# Hrafn_Top.net
KiCad netlist of a schematic drawn in Altium Designer
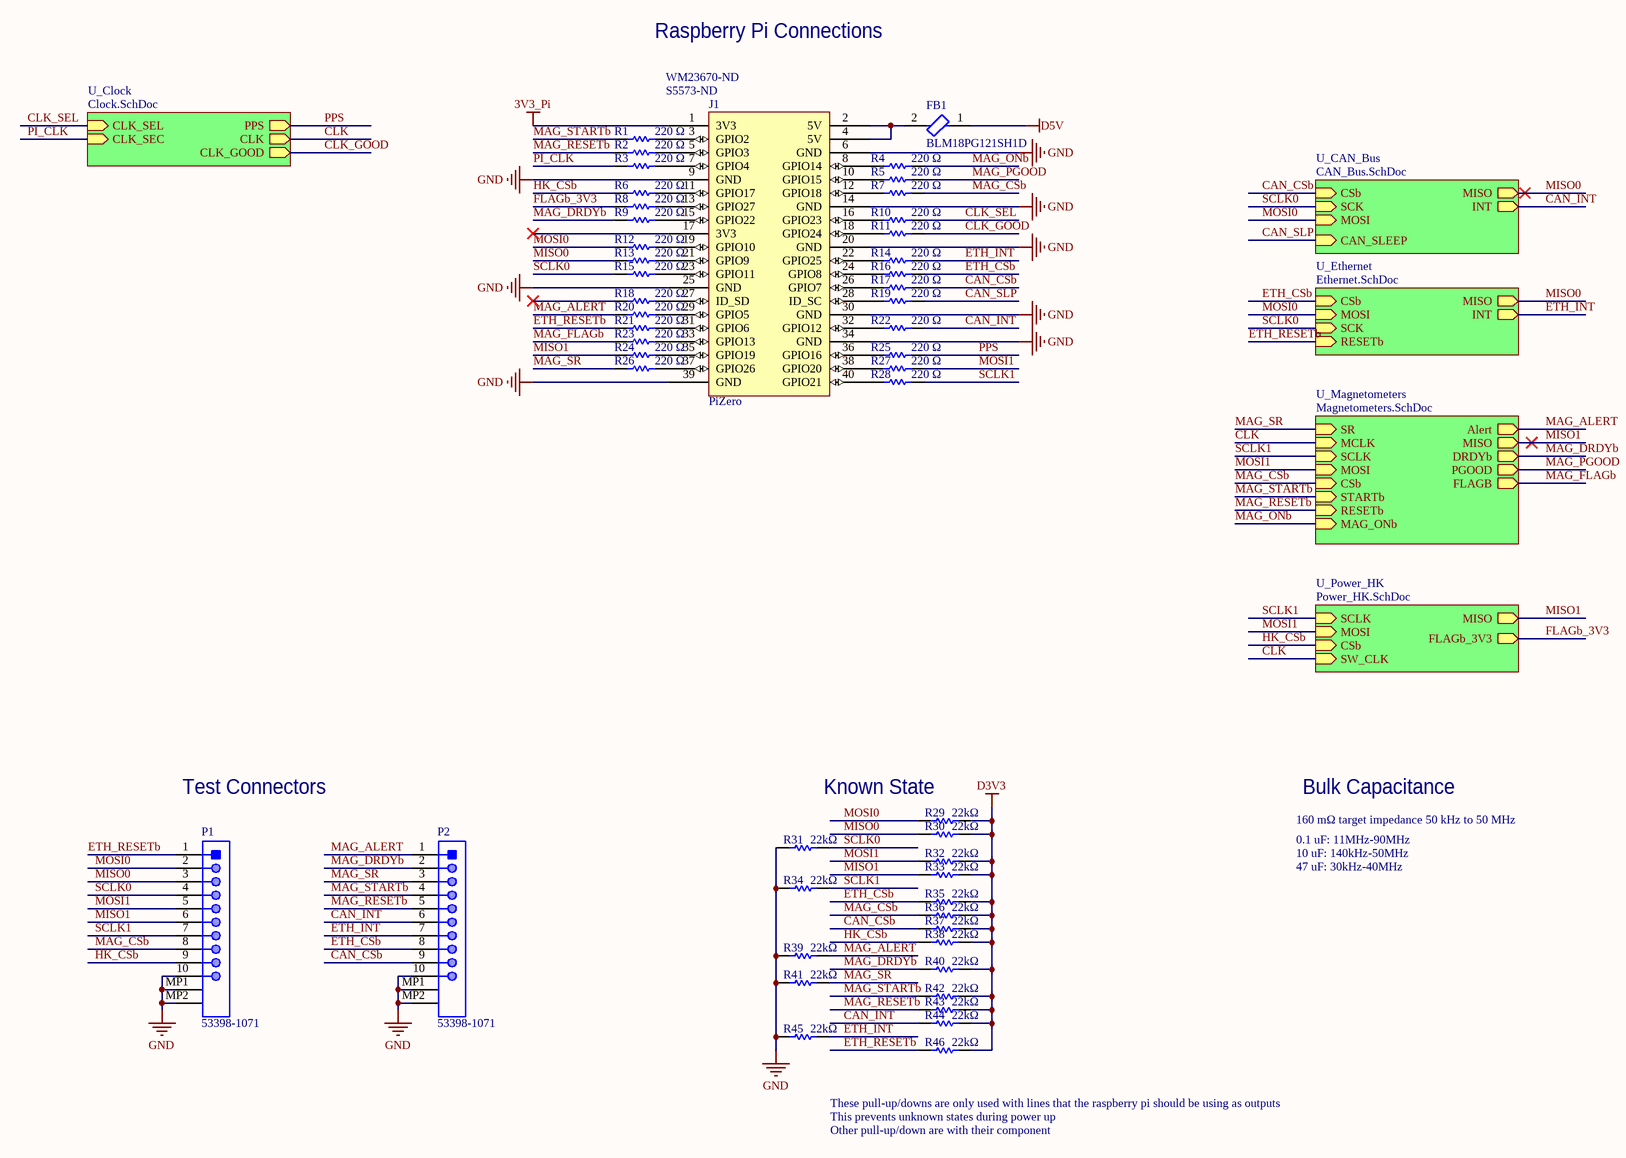
[diagram p0: Hrafn_Top.SchDoc]

(export (version "E")
  (design (tool "Eeschema 10.0.6"))
  (components
    (comp (ref "FB1")
      (value "BLM18PG121SH1D")
      (footprint "FP-BLM18-0_15-t0_8-IPC_C")
      (description "Chip Ferrite Bead, 0603, 120Ω @ 100MHz, 0.05Ω, 25%, 2A")
      (fields (field (name "TOLERANCE") "25%"))
      (libsource (lib "Altium Content Vault") (part "5f30dd21d616792df468990f7003faa"))
    )
    (comp (ref "J1")
      (value "PiZero")
      (footprint "DIP40")
      (fields
        (field (name "SUPPLIER PART NUMBER 1") "S5573-ND")
        (field (name "SUPPLIER PART NUMBER 2") "WM23670-ND")
      )
      (libsource (lib "Hrafn") (part "PiZero"))
    )
    (comp (ref "P1")
      (value "53398-1071")
      (footprint "MOLX-53398-1071_V")
      (description "Male Header, Pitch 1.25 mm, 1 x 10 Position, Height 4.7 mm, -40 to 85 degC, RoHS, Tape and Reel")
      (fields (field (name "MANUFACTURER") "Molex"))
      (libsource (lib "Altium Content Vault") (part "CN-1P-2M-R10"))
    )
    (comp (ref "P2")
      (value "53398-1071")
      (footprint "MOLX-53398-1071_V")
      (description "Male Header, Pitch 1.25 mm, 1 x 10 Position, Height 4.7 mm, -40 to 85 degC, RoHS, Tape and Reel")
      (fields (field (name "MANUFACTURER") "Molex"))
      (libsource (lib "Altium Content Vault") (part "CN-1P-2M-R10"))
    )
    (comp (ref "R1")
      (value "220 Ω")
      (footprint "RESC1005X40X25LL05T05")
      (fields (field (name "PART NUMBER") "CRCW040220K0FKED") (field (name "MANUFACTURER") "Vishay Dale"))
      (libsource (lib "Altium Content Vault") (part "RES"))
    )
    (comp (ref "R2")
      (value "220 Ω")
      (footprint "RESC1005X40X25LL05T05")
      (fields (field (name "PART NUMBER") "CRCW040220K0FKED") (field (name "MANUFACTURER") "Vishay Dale"))
      (libsource (lib "Altium Content Vault") (part "RES"))
    )
    (comp (ref "R3")
      (value "220 Ω")
      (footprint "RESC1005X40X25LL05T05")
      (fields (field (name "PART NUMBER") "CRCW040220K0FKED") (field (name "MANUFACTURER") "Vishay Dale"))
      (libsource (lib "Altium Content Vault") (part "RES"))
    )
    (comp (ref "R4")
      (value "220 Ω")
      (footprint "RESC1005X40X25LL05T05")
      (fields (field (name "PART NUMBER") "CRCW040220K0FKED") (field (name "MANUFACTURER") "Vishay Dale"))
      (libsource (lib "Altium Content Vault") (part "RES"))
    )
    (comp (ref "R5")
      (value "220 Ω")
      (footprint "RESC1005X40X25LL05T05")
      (fields (field (name "PART NUMBER") "CRCW040220K0FKED") (field (name "MANUFACTURER") "Vishay Dale"))
      (libsource (lib "Altium Content Vault") (part "RES"))
    )
    (comp (ref "R6")
      (value "220 Ω")
      (footprint "RESC1005X40X25LL05T05")
      (fields (field (name "PART NUMBER") "CRCW040220K0FKED") (field (name "MANUFACTURER") "Vishay Dale"))
      (libsource (lib "Altium Content Vault") (part "RES"))
    )
    (comp (ref "R7")
      (value "220 Ω")
      (footprint "RESC1005X40X25LL05T05")
      (fields (field (name "PART NUMBER") "CRCW040220K0FKED") (field (name "MANUFACTURER") "Vishay Dale"))
      (libsource (lib "Altium Content Vault") (part "RES"))
    )
    (comp (ref "R8")
      (value "220 Ω")
      (footprint "RESC1005X40X25LL05T05")
      (fields (field (name "PART NUMBER") "CRCW040220K0FKED") (field (name "MANUFACTURER") "Vishay Dale"))
      (libsource (lib "Altium Content Vault") (part "RES"))
    )
    (comp (ref "R9")
      (value "220 Ω")
      (footprint "RESC1005X40X25LL05T05")
      (fields (field (name "PART NUMBER") "CRCW040220K0FKED") (field (name "MANUFACTURER") "Vishay Dale"))
      (libsource (lib "Altium Content Vault") (part "RES"))
    )
    (comp (ref "R10")
      (value "220 Ω")
      (footprint "RESC1005X40X25LL05T05")
      (fields (field (name "PART NUMBER") "CRCW040220K0FKED") (field (name "MANUFACTURER") "Vishay Dale"))
      (libsource (lib "Altium Content Vault") (part "RES"))
    )
    (comp (ref "R11")
      (value "220 Ω")
      (footprint "RESC1005X40X25LL05T05")
      (fields (field (name "PART NUMBER") "CRCW040220K0FKED") (field (name "MANUFACTURER") "Vishay Dale"))
      (libsource (lib "Altium Content Vault") (part "RES"))
    )
    (comp (ref "R12")
      (value "220 Ω")
      (footprint "RESC1005X40X25LL05T05")
      (fields (field (name "PART NUMBER") "CRCW040220K0FKED") (field (name "MANUFACTURER") "Vishay Dale"))
      (libsource (lib "Altium Content Vault") (part "RES"))
    )
    (comp (ref "R13")
      (value "220 Ω")
      (footprint "RESC1005X40X25LL05T05")
      (fields (field (name "PART NUMBER") "CRCW040220K0FKED") (field (name "MANUFACTURER") "Vishay Dale"))
      (libsource (lib "Altium Content Vault") (part "RES"))
    )
    (comp (ref "R14")
      (value "220 Ω")
      (footprint "RESC1005X40X25LL05T05")
      (fields (field (name "PART NUMBER") "CRCW040220K0FKED") (field (name "MANUFACTURER") "Vishay Dale"))
      (libsource (lib "Altium Content Vault") (part "RES"))
    )
    (comp (ref "R15")
      (value "220 Ω")
      (footprint "RESC1005X40X25LL05T05")
      (fields (field (name "PART NUMBER") "CRCW040220K0FKED") (field (name "MANUFACTURER") "Vishay Dale"))
      (libsource (lib "Altium Content Vault") (part "RES"))
    )
    (comp (ref "R16")
      (value "220 Ω")
      (footprint "RESC1005X40X25LL05T05")
      (fields (field (name "PART NUMBER") "CRCW040220K0FKED") (field (name "MANUFACTURER") "Vishay Dale"))
      (libsource (lib "Altium Content Vault") (part "RES"))
    )
    (comp (ref "R17")
      (value "220 Ω")
      (footprint "RESC1005X40X25LL05T05")
      (fields (field (name "PART NUMBER") "CRCW040220K0FKED") (field (name "MANUFACTURER") "Vishay Dale"))
      (libsource (lib "Altium Content Vault") (part "RES"))
    )
    (comp (ref "R18")
      (value "220 Ω")
      (footprint "RESC1005X40X25LL05T05")
      (fields (field (name "PART NUMBER") "CRCW040220K0FKED") (field (name "MANUFACTURER") "Vishay Dale"))
      (libsource (lib "Altium Content Vault") (part "RES"))
    )
    (comp (ref "R19")
      (value "220 Ω")
      (footprint "RESC1005X40X25LL05T05")
      (fields (field (name "PART NUMBER") "CRCW040220K0FKED") (field (name "MANUFACTURER") "Vishay Dale"))
      (libsource (lib "Altium Content Vault") (part "RES"))
    )
    (comp (ref "R20")
      (value "220 Ω")
      (footprint "RESC1005X40X25LL05T05")
      (fields (field (name "PART NUMBER") "CRCW040220K0FKED") (field (name "MANUFACTURER") "Vishay Dale"))
      (libsource (lib "Altium Content Vault") (part "RES"))
    )
    (comp (ref "R21")
      (value "220 Ω")
      (footprint "RESC1005X40X25LL05T05")
      (fields (field (name "PART NUMBER") "CRCW040220K0FKED") (field (name "MANUFACTURER") "Vishay Dale"))
      (libsource (lib "Altium Content Vault") (part "RES"))
    )
    (comp (ref "R22")
      (value "220 Ω")
      (footprint "RESC1005X40X25LL05T05")
      (fields (field (name "PART NUMBER") "CRCW040220K0FKED") (field (name "MANUFACTURER") "Vishay Dale"))
      (libsource (lib "Altium Content Vault") (part "RES"))
    )
    (comp (ref "R23")
      (value "220 Ω")
      (footprint "RESC1005X40X25LL05T05")
      (fields (field (name "PART NUMBER") "CRCW040220K0FKED") (field (name "MANUFACTURER") "Vishay Dale"))
      (libsource (lib "Altium Content Vault") (part "RES"))
    )
    (comp (ref "R24")
      (value "220 Ω")
      (footprint "RESC1005X40X25LL05T05")
      (fields (field (name "PART NUMBER") "CRCW040220K0FKED") (field (name "MANUFACTURER") "Vishay Dale"))
      (libsource (lib "Altium Content Vault") (part "RES"))
    )
    (comp (ref "R25")
      (value "220 Ω")
      (footprint "RESC1005X40X25LL05T05")
      (fields (field (name "PART NUMBER") "CRCW040220K0FKED") (field (name "MANUFACTURER") "Vishay Dale"))
      (libsource (lib "Altium Content Vault") (part "RES"))
    )
    (comp (ref "R26")
      (value "220 Ω")
      (footprint "RESC1005X40X25LL05T05")
      (fields (field (name "PART NUMBER") "CRCW040220K0FKED") (field (name "MANUFACTURER") "Vishay Dale"))
      (libsource (lib "Altium Content Vault") (part "RES"))
    )
    (comp (ref "R27")
      (value "220 Ω")
      (footprint "RESC1005X40X25LL05T05")
      (fields (field (name "PART NUMBER") "CRCW040220K0FKED") (field (name "MANUFACTURER") "Vishay Dale"))
      (libsource (lib "Altium Content Vault") (part "RES"))
    )
    (comp (ref "R28")
      (value "220 Ω")
      (footprint "RESC1005X40X25LL05T05")
      (fields (field (name "PART NUMBER") "CRCW040220K0FKED") (field (name "MANUFACTURER") "Vishay Dale"))
      (libsource (lib "Altium Content Vault") (part "RES"))
    )
    (comp (ref "R29")
      (value "22kΩ")
      (footprint "RESC1005X40X25LL05T05")
      (fields (field (name "MANUFACTURER") "Panasonic") (field (name "PART NUMBER") "ERJ-2GEJ223X"))
      (libsource (lib "Altium Content Vault") (part "RES"))
    )
    (comp (ref "R30")
      (value "22kΩ")
      (footprint "RESC1005X40X25LL05T05")
      (fields (field (name "MANUFACTURER") "Panasonic") (field (name "PART NUMBER") "ERJ-2GEJ223X"))
      (libsource (lib "Altium Content Vault") (part "RES"))
    )
    (comp (ref "R31")
      (value "22kΩ")
      (footprint "RESC1005X40X25LL05T05")
      (fields (field (name "MANUFACTURER") "Panasonic") (field (name "PART NUMBER") "ERJ-2GEJ223X"))
      (libsource (lib "Altium Content Vault") (part "RES"))
    )
    (comp (ref "R32")
      (value "22kΩ")
      (footprint "RESC1005X40X25LL05T05")
      (fields (field (name "MANUFACTURER") "Panasonic") (field (name "PART NUMBER") "ERJ-2GEJ223X"))
      (libsource (lib "Altium Content Vault") (part "RES"))
    )
    (comp (ref "R33")
      (value "22kΩ")
      (footprint "RESC1005X40X25LL05T05")
      (fields (field (name "MANUFACTURER") "Panasonic") (field (name "PART NUMBER") "ERJ-2GEJ223X"))
      (libsource (lib "Altium Content Vault") (part "RES"))
    )
    (comp (ref "R34")
      (value "22kΩ")
      (footprint "RESC1005X40X25LL05T05")
      (fields (field (name "MANUFACTURER") "Panasonic") (field (name "PART NUMBER") "ERJ-2GEJ223X"))
      (libsource (lib "Altium Content Vault") (part "RES"))
    )
    (comp (ref "R35")
      (value "22kΩ")
      (footprint "RESC1005X40X25LL05T05")
      (fields (field (name "MANUFACTURER") "Panasonic") (field (name "PART NUMBER") "ERJ-2GEJ223X"))
      (libsource (lib "Altium Content Vault") (part "RES"))
    )
    (comp (ref "R36")
      (value "22kΩ")
      (footprint "RESC1005X40X25LL05T05")
      (fields (field (name "MANUFACTURER") "Panasonic") (field (name "PART NUMBER") "ERJ-2GEJ223X"))
      (libsource (lib "Altium Content Vault") (part "RES"))
    )
    (comp (ref "R37")
      (value "22kΩ")
      (footprint "RESC1005X40X25LL05T05")
      (fields (field (name "MANUFACTURER") "Panasonic") (field (name "PART NUMBER") "ERJ-2GEJ223X"))
      (libsource (lib "Altium Content Vault") (part "RES"))
    )
    (comp (ref "R38")
      (value "22kΩ")
      (footprint "RESC1005X40X25LL05T05")
      (fields (field (name "MANUFACTURER") "Panasonic") (field (name "PART NUMBER") "ERJ-2GEJ223X"))
      (libsource (lib "Altium Content Vault") (part "RES"))
    )
    (comp (ref "R39")
      (value "22kΩ")
      (footprint "RESC1005X40X25LL05T05")
      (fields (field (name "MANUFACTURER") "Panasonic") (field (name "PART NUMBER") "ERJ-2GEJ223X"))
      (libsource (lib "Altium Content Vault") (part "RES"))
    )
    (comp (ref "R40")
      (value "22kΩ")
      (footprint "RESC1005X40X25LL05T05")
      (fields (field (name "MANUFACTURER") "Panasonic") (field (name "PART NUMBER") "ERJ-2GEJ223X"))
      (libsource (lib "Altium Content Vault") (part "RES"))
    )
    (comp (ref "R41")
      (value "22kΩ")
      (footprint "RESC1005X40X25LL05T05")
      (fields (field (name "MANUFACTURER") "Panasonic") (field (name "PART NUMBER") "ERJ-2GEJ223X"))
      (libsource (lib "Altium Content Vault") (part "RES"))
    )
    (comp (ref "R42")
      (value "22kΩ")
      (footprint "RESC1005X40X25LL05T05")
      (fields (field (name "MANUFACTURER") "Panasonic") (field (name "PART NUMBER") "ERJ-2GEJ223X"))
      (libsource (lib "Altium Content Vault") (part "RES"))
    )
    (comp (ref "R43")
      (value "22kΩ")
      (footprint "RESC1005X40X25LL05T05")
      (fields (field (name "MANUFACTURER") "Panasonic") (field (name "PART NUMBER") "ERJ-2GEJ223X"))
      (libsource (lib "Altium Content Vault") (part "RES"))
    )
    (comp (ref "R44")
      (value "22kΩ")
      (footprint "RESC1005X40X25LL05T05")
      (fields (field (name "MANUFACTURER") "Panasonic") (field (name "PART NUMBER") "ERJ-2GEJ223X"))
      (libsource (lib "Altium Content Vault") (part "RES"))
    )
    (comp (ref "R45")
      (value "22kΩ")
      (footprint "RESC1005X40X25LL05T05")
      (fields (field (name "MANUFACTURER") "Panasonic") (field (name "PART NUMBER") "ERJ-2GEJ223X"))
      (libsource (lib "Altium Content Vault") (part "RES"))
    )
    (comp (ref "R46")
      (value "22kΩ")
      (footprint "RESC1005X40X25LL05T05")
      (fields (field (name "MANUFACTURER") "Panasonic") (field (name "PART NUMBER") "ERJ-2GEJ223X"))
      (libsource (lib "Altium Content Vault") (part "RES"))
    )
  )
  (nets
    (net (code "1") (name "/CAN_CSb") (class "Default")
      (node (ref "P2") (pin "9") (pinfunction "9_9") (pintype "passive"))
      (node (ref "R17") (pin "2") (pinfunction "2_2") (pintype "passive"))
      (node (ref "R37") (pin "1") (pinfunction "1_1") (pintype "passive"))
    )
    (net (code "2") (name "/CAN_INT") (class "Default")
      (node (ref "P2") (pin "6") (pinfunction "6_6") (pintype "passive"))
      (node (ref "R22") (pin "2") (pinfunction "2_2") (pintype "passive"))
      (node (ref "R44") (pin "1") (pinfunction "1_1") (pintype "passive"))
    )
    (net (code "3") (name "/CAN_SLP") (class "Default")
      (node (ref "R19") (pin "2") (pinfunction "2_2") (pintype "passive"))
    )
    (net (code "5") (name "/CLK_GOOD") (class "Default")
      (node (ref "R11") (pin "2") (pinfunction "2_2") (pintype "passive"))
    )
    (net (code "6") (name "/CLK_SEL") (class "Default")
      (node (ref "R10") (pin "2") (pinfunction "2_2") (pintype "passive"))
    )
    (net (code "7") (name "/ETH_CSb") (class "Default")
      (node (ref "P2") (pin "8") (pinfunction "8_8") (pintype "passive"))
      (node (ref "R16") (pin "2") (pinfunction "2_2") (pintype "passive"))
      (node (ref "R35") (pin "1") (pinfunction "1_1") (pintype "passive"))
    )
    (net (code "8") (name "/ETH_INT") (class "Default")
      (node (ref "P2") (pin "7") (pinfunction "7_7") (pintype "passive"))
      (node (ref "R14") (pin "2") (pinfunction "2_2") (pintype "passive"))
      (node (ref "R45") (pin "2") (pinfunction "2_2") (pintype "passive"))
    )
    (net (code "9") (name "/ETH_RESETb") (class "Default")
      (node (ref "P1") (pin "1") (pinfunction "1_1") (pintype "passive"))
      (node (ref "R21") (pin "1") (pinfunction "1_1") (pintype "passive"))
      (node (ref "R46") (pin "1") (pinfunction "1_1") (pintype "passive"))
    )
    (net (code "10") (name "/FLAGb_3V3") (class "Default")
      (node (ref "R8") (pin "1") (pinfunction "1_1") (pintype "passive"))
    )
    (net (code "11") (name "/HK_CSb") (class "Default")
      (node (ref "P1") (pin "9") (pinfunction "9_9") (pintype "passive"))
      (node (ref "R38") (pin "1") (pinfunction "1_1") (pintype "passive"))
      (node (ref "R6") (pin "1") (pinfunction "1_1") (pintype "passive"))
    )
    (net (code "12") (name "/MAG_ALERT") (class "Default")
      (node (ref "P2") (pin "1") (pinfunction "1_1") (pintype "passive"))
      (node (ref "R20") (pin "1") (pinfunction "1_1") (pintype "passive"))
      (node (ref "R39") (pin "2") (pinfunction "2_2") (pintype "passive"))
    )
    (net (code "13") (name "/MAG_CSb") (class "Default")
      (node (ref "P1") (pin "8") (pinfunction "8_8") (pintype "passive"))
      (node (ref "R36") (pin "1") (pinfunction "1_1") (pintype "passive"))
      (node (ref "R7") (pin "2") (pinfunction "2_2") (pintype "passive"))
    )
    (net (code "14") (name "/MAG_DRDYb") (class "Default")
      (node (ref "P2") (pin "2") (pinfunction "2_2") (pintype "passive"))
      (node (ref "R40") (pin "1") (pinfunction "1_1") (pintype "passive"))
      (node (ref "R9") (pin "1") (pinfunction "1_1") (pintype "passive"))
    )
    (net (code "15") (name "/MAG_FLAGb") (class "Default")
      (node (ref "R23") (pin "1") (pinfunction "1_1") (pintype "passive"))
    )
    (net (code "16") (name "/MAG_ONb") (class "Default")
      (node (ref "R4") (pin "2") (pinfunction "2_2") (pintype "passive"))
    )
    (net (code "17") (name "/MAG_PGOOD") (class "Default")
      (node (ref "R5") (pin "2") (pinfunction "2_2") (pintype "passive"))
    )
    (net (code "18") (name "/MAG_RESETb") (class "Default")
      (node (ref "P2") (pin "5") (pinfunction "5_5") (pintype "passive"))
      (node (ref "R2") (pin "1") (pinfunction "1_1") (pintype "passive"))
      (node (ref "R43") (pin "1") (pinfunction "1_1") (pintype "passive"))
    )
    (net (code "19") (name "/MAG_SR") (class "Default")
      (node (ref "P2") (pin "3") (pinfunction "3_3") (pintype "passive"))
      (node (ref "R26") (pin "1") (pinfunction "1_1") (pintype "passive"))
      (node (ref "R41") (pin "2") (pinfunction "2_2") (pintype "passive"))
    )
    (net (code "20") (name "/MAG_STARTb") (class "Default")
      (node (ref "P2") (pin "4") (pinfunction "4_4") (pintype "passive"))
      (node (ref "R1") (pin "1") (pinfunction "1_1") (pintype "passive"))
      (node (ref "R42") (pin "1") (pinfunction "1_1") (pintype "passive"))
    )
    (net (code "21") (name "/MISO0") (class "Default")
      (node (ref "P1") (pin "3") (pinfunction "3_3") (pintype "passive"))
      (node (ref "R13") (pin "1") (pinfunction "1_1") (pintype "passive"))
      (node (ref "R30") (pin "1") (pinfunction "1_1") (pintype "passive"))
    )
    (net (code "22") (name "/MISO1") (class "Default")
      (node (ref "P1") (pin "6") (pinfunction "6_6") (pintype "passive"))
      (node (ref "R24") (pin "1") (pinfunction "1_1") (pintype "passive"))
      (node (ref "R33") (pin "1") (pinfunction "1_1") (pintype "passive"))
    )
    (net (code "23") (name "/MOSI0") (class "Default")
      (node (ref "P1") (pin "2") (pinfunction "2_2") (pintype "passive"))
      (node (ref "R12") (pin "1") (pinfunction "1_1") (pintype "passive"))
      (node (ref "R29") (pin "1") (pinfunction "1_1") (pintype "passive"))
    )
    (net (code "24") (name "/MOSI1") (class "Default")
      (node (ref "P1") (pin "5") (pinfunction "5_5") (pintype "passive"))
      (node (ref "R27") (pin "2") (pinfunction "2_2") (pintype "passive"))
      (node (ref "R32") (pin "1") (pinfunction "1_1") (pintype "passive"))
    )
    (net (code "25") (name "/PI_CLK") (class "Default")
      (node (ref "R3") (pin "1") (pinfunction "1_1") (pintype "passive"))
    )
    (net (code "26") (name "/PPS") (class "Default")
      (node (ref "R25") (pin "2") (pinfunction "2_2") (pintype "passive"))
    )
    (net (code "27") (name "/SCLK0") (class "Default")
      (node (ref "P1") (pin "4") (pinfunction "4_4") (pintype "passive"))
      (node (ref "R15") (pin "1") (pinfunction "1_1") (pintype "passive"))
      (node (ref "R31") (pin "2") (pinfunction "2_2") (pintype "passive"))
    )
    (net (code "28") (name "/SCLK1") (class "Default")
      (node (ref "P1") (pin "7") (pinfunction "7_7") (pintype "passive"))
      (node (ref "R28") (pin "2") (pinfunction "2_2") (pintype "passive"))
      (node (ref "R34") (pin "2") (pinfunction "2_2") (pintype "passive"))
    )
    (net (code "29") (name "3V3_Pi") (class "Default")
      (node (ref "J1") (pin "1") (pinfunction "3V3_1") (pintype "power_in"))
    )
    (net (code "30") (name "D3V3") (class "Default")
      (node (ref "R29") (pin "2") (pinfunction "2_2") (pintype "passive"))
      (node (ref "R30") (pin "2") (pinfunction "2_2") (pintype "passive"))
      (node (ref "R32") (pin "2") (pinfunction "2_2") (pintype "passive"))
      (node (ref "R33") (pin "2") (pinfunction "2_2") (pintype "passive"))
      (node (ref "R35") (pin "2") (pinfunction "2_2") (pintype "passive"))
      (node (ref "R36") (pin "2") (pinfunction "2_2") (pintype "passive"))
      (node (ref "R37") (pin "2") (pinfunction "2_2") (pintype "passive"))
      (node (ref "R38") (pin "2") (pinfunction "2_2") (pintype "passive"))
      (node (ref "R40") (pin "2") (pinfunction "2_2") (pintype "passive"))
      (node (ref "R42") (pin "2") (pinfunction "2_2") (pintype "passive"))
      (node (ref "R43") (pin "2") (pinfunction "2_2") (pintype "passive"))
      (node (ref "R44") (pin "2") (pinfunction "2_2") (pintype "passive"))
      (node (ref "R46") (pin "2") (pinfunction "2_2") (pintype "passive"))
    )
    (net (code "31") (name "D5V") (class "Default")
      (node (ref "FB1") (pin "1") (pinfunction "1_1") (pintype "passive"))
    )
    (net (code "32") (name "GND") (class "Default")
      (node (ref "J1") (pin "14") (pinfunction "GND_14") (pintype "power_in"))
      (node (ref "J1") (pin "20") (pinfunction "GND_20") (pintype "power_in"))
      (node (ref "J1") (pin "25") (pinfunction "GND_25") (pintype "power_in"))
      (node (ref "J1") (pin "30") (pinfunction "GND_30") (pintype "power_in"))
      (node (ref "J1") (pin "34") (pinfunction "GND_34") (pintype "power_in"))
      (node (ref "J1") (pin "39") (pinfunction "GND_39") (pintype "power_in"))
      (node (ref "J1") (pin "6") (pinfunction "GND_6") (pintype "power_in"))
      (node (ref "J1") (pin "9") (pinfunction "GND_9") (pintype "power_in"))
      (node (ref "P1") (pin "10") (pinfunction "10_10") (pintype "passive"))
      (node (ref "P1") (pin "MP1") (pinfunction "MP1_MP1") (pintype "passive"))
      (node (ref "P1") (pin "MP2") (pinfunction "MP2_MP2") (pintype "passive"))
      (node (ref "P2") (pin "10") (pinfunction "10_10") (pintype "passive"))
      (node (ref "P2") (pin "MP1") (pinfunction "MP1_MP1") (pintype "passive"))
      (node (ref "P2") (pin "MP2") (pinfunction "MP2_MP2") (pintype "passive"))
      (node (ref "R31") (pin "1") (pinfunction "1_1") (pintype "passive"))
      (node (ref "R34") (pin "1") (pinfunction "1_1") (pintype "passive"))
      (node (ref "R39") (pin "1") (pinfunction "1_1") (pintype "passive"))
      (node (ref "R41") (pin "1") (pinfunction "1_1") (pintype "passive"))
      (node (ref "R45") (pin "1") (pinfunction "1_1") (pintype "passive"))
    )
    (net (code "33") (name "Net-(FB1-Pad2)") (class "Default")
      (node (ref "FB1") (pin "2") (pinfunction "2_2") (pintype "passive"))
      (node (ref "J1") (pin "2") (pinfunction "5V_2") (pintype "power_in"))
      (node (ref "J1") (pin "4") (pinfunction "5V_4") (pintype "power_in"))
    )
    (net (code "34") (name "Net-(J1-GPIO2)") (class "Default")
      (node (ref "J1") (pin "3") (pinfunction "GPIO2_3") (pintype "bidirectional"))
      (node (ref "R1") (pin "2") (pinfunction "2_2") (pintype "passive"))
    )
    (net (code "35") (name "Net-(J1-GPIO3)") (class "Default")
      (node (ref "J1") (pin "5") (pinfunction "GPIO3_5") (pintype "bidirectional"))
      (node (ref "R2") (pin "2") (pinfunction "2_2") (pintype "passive"))
    )
    (net (code "36") (name "Net-(J1-GPIO4)") (class "Default")
      (node (ref "J1") (pin "7") (pinfunction "GPIO4_7") (pintype "bidirectional"))
      (node (ref "R3") (pin "2") (pinfunction "2_2") (pintype "passive"))
    )
    (net (code "37") (name "Net-(J1-GPIO5)") (class "Default")
      (node (ref "J1") (pin "29") (pinfunction "GPIO5_29") (pintype "bidirectional"))
      (node (ref "R20") (pin "2") (pinfunction "2_2") (pintype "passive"))
    )
    (net (code "38") (name "Net-(J1-GPIO6)") (class "Default")
      (node (ref "J1") (pin "31") (pinfunction "GPIO6_31") (pintype "bidirectional"))
      (node (ref "R21") (pin "2") (pinfunction "2_2") (pintype "passive"))
    )
    (net (code "39") (name "Net-(J1-GPIO7)") (class "Default")
      (node (ref "J1") (pin "26") (pinfunction "GPIO7_26") (pintype "bidirectional"))
      (node (ref "R17") (pin "1") (pinfunction "1_1") (pintype "passive"))
    )
    (net (code "40") (name "Net-(J1-GPIO8)") (class "Default")
      (node (ref "J1") (pin "24") (pinfunction "GPIO8_24") (pintype "bidirectional"))
      (node (ref "R16") (pin "1") (pinfunction "1_1") (pintype "passive"))
    )
    (net (code "41") (name "Net-(J1-GPIO9)") (class "Default")
      (node (ref "J1") (pin "21") (pinfunction "GPIO9_21") (pintype "bidirectional"))
      (node (ref "R13") (pin "2") (pinfunction "2_2") (pintype "passive"))
    )
    (net (code "42") (name "Net-(J1-GPIO10)") (class "Default")
      (node (ref "J1") (pin "19") (pinfunction "GPIO10_19") (pintype "bidirectional"))
      (node (ref "R12") (pin "2") (pinfunction "2_2") (pintype "passive"))
    )
    (net (code "43") (name "Net-(J1-GPIO11)") (class "Default")
      (node (ref "J1") (pin "23") (pinfunction "GPIO11_23") (pintype "bidirectional"))
      (node (ref "R15") (pin "2") (pinfunction "2_2") (pintype "passive"))
    )
    (net (code "44") (name "Net-(J1-GPIO12)") (class "Default")
      (node (ref "J1") (pin "32") (pinfunction "GPIO12_32") (pintype "bidirectional"))
      (node (ref "R22") (pin "1") (pinfunction "1_1") (pintype "passive"))
    )
    (net (code "45") (name "Net-(J1-GPIO13)") (class "Default")
      (node (ref "J1") (pin "33") (pinfunction "GPIO13_33") (pintype "bidirectional"))
      (node (ref "R23") (pin "2") (pinfunction "2_2") (pintype "passive"))
    )
    (net (code "46") (name "Net-(J1-GPIO14)") (class "Default")
      (node (ref "J1") (pin "8") (pinfunction "GPIO14_8") (pintype "bidirectional"))
      (node (ref "R4") (pin "1") (pinfunction "1_1") (pintype "passive"))
    )
    (net (code "47") (name "Net-(J1-GPIO15)") (class "Default")
      (node (ref "J1") (pin "10") (pinfunction "GPIO15_10") (pintype "bidirectional"))
      (node (ref "R5") (pin "1") (pinfunction "1_1") (pintype "passive"))
    )
    (net (code "48") (name "Net-(J1-GPIO16)") (class "Default")
      (node (ref "J1") (pin "36") (pinfunction "GPIO16_36") (pintype "bidirectional"))
      (node (ref "R25") (pin "1") (pinfunction "1_1") (pintype "passive"))
    )
    (net (code "49") (name "Net-(J1-GPIO17)") (class "Default")
      (node (ref "J1") (pin "11") (pinfunction "GPIO17_11") (pintype "bidirectional"))
      (node (ref "R6") (pin "2") (pinfunction "2_2") (pintype "passive"))
    )
    (net (code "50") (name "Net-(J1-GPIO18)") (class "Default")
      (node (ref "J1") (pin "12") (pinfunction "GPIO18_12") (pintype "bidirectional"))
      (node (ref "R7") (pin "1") (pinfunction "1_1") (pintype "passive"))
    )
    (net (code "51") (name "Net-(J1-GPIO19)") (class "Default")
      (node (ref "J1") (pin "35") (pinfunction "GPIO19_35") (pintype "bidirectional"))
      (node (ref "R24") (pin "2") (pinfunction "2_2") (pintype "passive"))
    )
    (net (code "52") (name "Net-(J1-GPIO20)") (class "Default")
      (node (ref "J1") (pin "38") (pinfunction "GPIO20_38") (pintype "bidirectional"))
      (node (ref "R27") (pin "1") (pinfunction "1_1") (pintype "passive"))
    )
    (net (code "53") (name "Net-(J1-GPIO21)") (class "Default")
      (node (ref "J1") (pin "40") (pinfunction "GPIO21_40") (pintype "bidirectional"))
      (node (ref "R28") (pin "1") (pinfunction "1_1") (pintype "passive"))
    )
    (net (code "54") (name "Net-(J1-GPIO22)") (class "Default")
      (node (ref "J1") (pin "15") (pinfunction "GPIO22_15") (pintype "bidirectional"))
      (node (ref "R9") (pin "2") (pinfunction "2_2") (pintype "passive"))
    )
    (net (code "55") (name "Net-(J1-GPIO23)") (class "Default")
      (node (ref "J1") (pin "16") (pinfunction "GPIO23_16") (pintype "bidirectional"))
      (node (ref "R10") (pin "1") (pinfunction "1_1") (pintype "passive"))
    )
    (net (code "56") (name "Net-(J1-GPIO24)") (class "Default")
      (node (ref "J1") (pin "18") (pinfunction "GPIO24_18") (pintype "bidirectional"))
      (node (ref "R11") (pin "1") (pinfunction "1_1") (pintype "passive"))
    )
    (net (code "57") (name "Net-(J1-GPIO25)") (class "Default")
      (node (ref "J1") (pin "22") (pinfunction "GPIO25_22") (pintype "bidirectional"))
      (node (ref "R14") (pin "1") (pinfunction "1_1") (pintype "passive"))
    )
    (net (code "58") (name "Net-(J1-GPIO26)") (class "Default")
      (node (ref "J1") (pin "37") (pinfunction "GPIO26_37") (pintype "bidirectional"))
      (node (ref "R26") (pin "2") (pinfunction "2_2") (pintype "passive"))
    )
    (net (code "59") (name "Net-(J1-GPIO27)") (class "Default")
      (node (ref "J1") (pin "13") (pinfunction "GPIO27_13") (pintype "bidirectional"))
      (node (ref "R8") (pin "2") (pinfunction "2_2") (pintype "passive"))
    )
    (net (code "60") (name "Net-(J1-ID_SC)") (class "Default")
      (node (ref "J1") (pin "28") (pinfunction "ID_SC_28") (pintype "bidirectional"))
      (node (ref "R19") (pin "1") (pinfunction "1_1") (pintype "passive"))
    )
    (net (code "61") (name "Net-(J1-ID_SD)") (class "Default")
      (node (ref "J1") (pin "27") (pinfunction "ID_SD_27") (pintype "bidirectional"))
      (node (ref "R18") (pin "2") (pinfunction "2_2") (pintype "passive"))
    )
    (net (code "62") (name "unconnected-(J1-3V3-Pad17)") (class "Default")
      (node (ref "J1") (pin "17") (pinfunction "3V3_17") (pintype "power_in+no_connect"))
    )
    (net (code "63") (name "unconnected-(R18-Pad1)") (class "Default")
      (node (ref "R18") (pin "1") (pinfunction "1_1") (pintype "passive+no_connect"))
    )
  )
)
